# S07_PCIe_Connector.net
KiCad netlist of a schematic drawn in Altium Designer
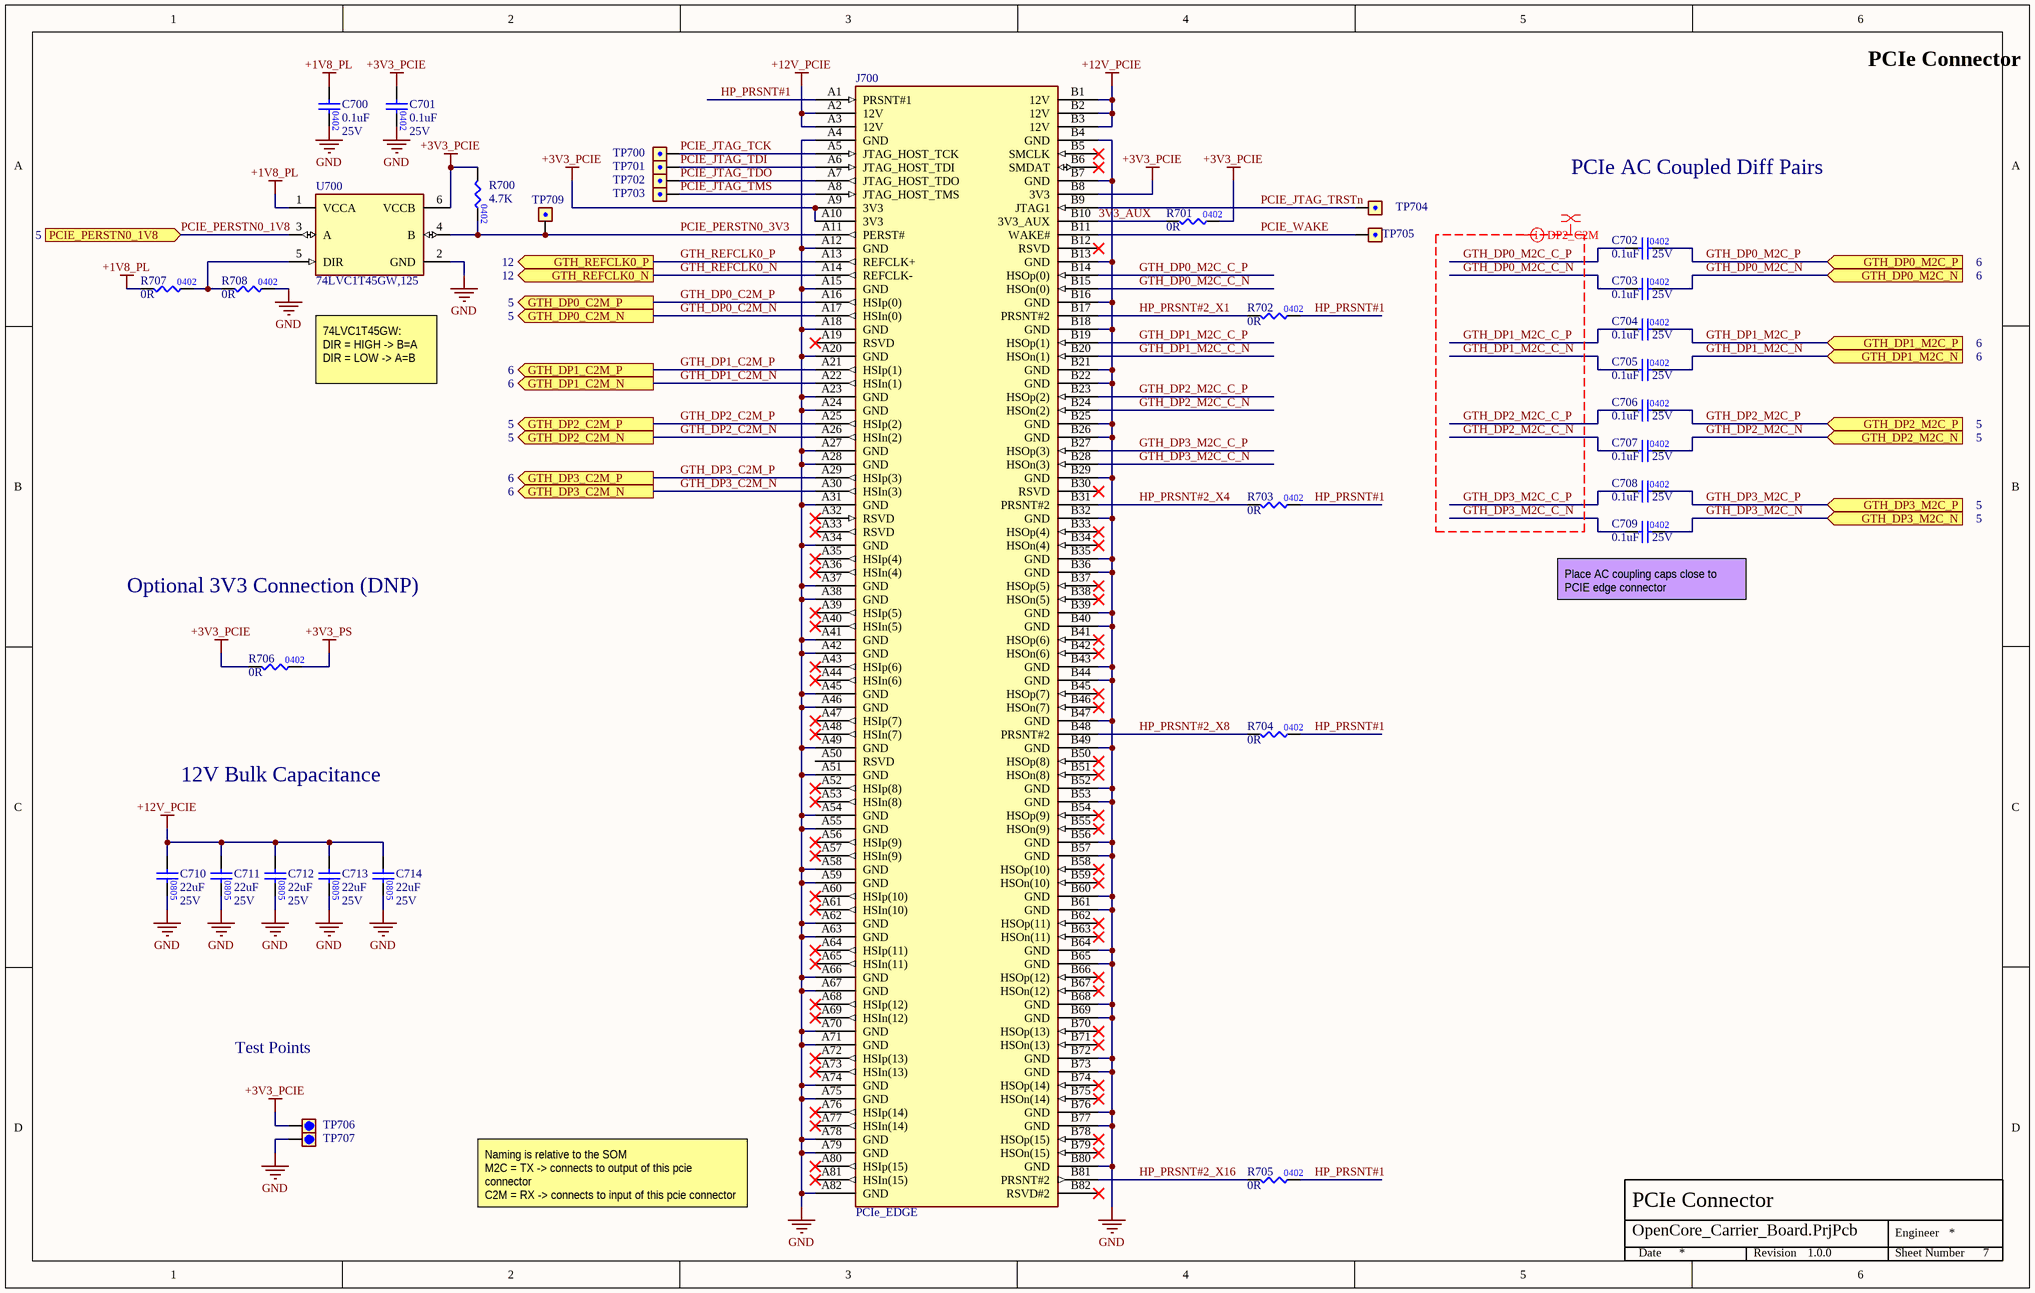
[diagram p0: S07_PCIe_Connector.SchDoc]

(export (version "E")
  (design (tool "Eeschema 10.0.6"))
  (components
    (comp (ref "C700")
      (value "0.1uF")
      (footprint "CAP0402")
      (description "CAP CER 0.1UF 25V X5R 0402")
      (fields
        (field (name "MANUFACTURER") "Samsung Electro-Mechanics")
        (field (name "TOLERANCE") "10%")
        (field (name "VOLTAGE RATING") "25V")
      )
      (libsource (lib "OpenCore_Sch_Lib") (part "CAP_CL05A104KA5NNNC"))
    )
    (comp (ref "C701")
      (value "0.1uF")
      (footprint "CAP0402")
      (description "CAP CER 0.1UF 25V X5R 0402")
      (fields
        (field (name "MANUFACTURER") "Samsung Electro-Mechanics")
        (field (name "TOLERANCE") "10%")
        (field (name "VOLTAGE RATING") "25V")
      )
      (libsource (lib "OpenCore_Sch_Lib") (part "CAP_CL05A104KA5NNNC"))
    )
    (comp (ref "C702")
      (value "0.1uF")
      (footprint "CAP0402")
      (description "CAP CER 0.1UF 25V X5R 0402")
      (fields
        (field (name "MANUFACTURER") "Samsung Electro-Mechanics")
        (field (name "TOLERANCE") "10%")
        (field (name "VOLTAGE RATING") "25V")
      )
      (libsource (lib "OpenCore_Sch_Lib") (part "CAP_CL05A104KA5NNNC"))
    )
    (comp (ref "C703")
      (value "0.1uF")
      (footprint "CAP0402")
      (description "CAP CER 0.1UF 25V X5R 0402")
      (fields
        (field (name "MANUFACTURER") "Samsung Electro-Mechanics")
        (field (name "TOLERANCE") "10%")
        (field (name "VOLTAGE RATING") "25V")
      )
      (libsource (lib "OpenCore_Sch_Lib") (part "CAP_CL05A104KA5NNNC"))
    )
    (comp (ref "C704")
      (value "0.1uF")
      (footprint "CAP0402")
      (description "CAP CER 0.1UF 25V X5R 0402")
      (fields
        (field (name "MANUFACTURER") "Samsung Electro-Mechanics")
        (field (name "TOLERANCE") "10%")
        (field (name "VOLTAGE RATING") "25V")
      )
      (libsource (lib "OpenCore_Sch_Lib") (part "CAP_CL05A104KA5NNNC"))
    )
    (comp (ref "C705")
      (value "0.1uF")
      (footprint "CAP0402")
      (description "CAP CER 0.1UF 25V X5R 0402")
      (fields
        (field (name "MANUFACTURER") "Samsung Electro-Mechanics")
        (field (name "TOLERANCE") "10%")
        (field (name "VOLTAGE RATING") "25V")
      )
      (libsource (lib "OpenCore_Sch_Lib") (part "CAP_CL05A104KA5NNNC"))
    )
    (comp (ref "C706")
      (value "0.1uF")
      (footprint "CAP0402")
      (description "CAP CER 0.1UF 25V X5R 0402")
      (fields
        (field (name "MANUFACTURER") "Samsung Electro-Mechanics")
        (field (name "TOLERANCE") "10%")
        (field (name "VOLTAGE RATING") "25V")
      )
      (libsource (lib "OpenCore_Sch_Lib") (part "CAP_CL05A104KA5NNNC"))
    )
    (comp (ref "C707")
      (value "0.1uF")
      (footprint "CAP0402")
      (description "CAP CER 0.1UF 25V X5R 0402")
      (fields
        (field (name "MANUFACTURER") "Samsung Electro-Mechanics")
        (field (name "TOLERANCE") "10%")
        (field (name "VOLTAGE RATING") "25V")
      )
      (libsource (lib "OpenCore_Sch_Lib") (part "CAP_CL05A104KA5NNNC"))
    )
    (comp (ref "C708")
      (value "0.1uF")
      (footprint "CAP0402")
      (description "CAP CER 0.1UF 25V X5R 0402")
      (fields
        (field (name "MANUFACTURER") "Samsung Electro-Mechanics")
        (field (name "TOLERANCE") "10%")
        (field (name "VOLTAGE RATING") "25V")
      )
      (libsource (lib "OpenCore_Sch_Lib") (part "CAP_CL05A104KA5NNNC"))
    )
    (comp (ref "C709")
      (value "0.1uF")
      (footprint "CAP0402")
      (description "CAP CER 0.1UF 25V X5R 0402")
      (fields
        (field (name "MANUFACTURER") "Samsung Electro-Mechanics")
        (field (name "TOLERANCE") "10%")
        (field (name "VOLTAGE RATING") "25V")
      )
      (libsource (lib "OpenCore_Sch_Lib") (part "CAP_CL05A104KA5NNNC"))
    )
    (comp (ref "C710")
      (value "22uF")
      (footprint "CAP0805")
      (description "CAP CER 22UF 25V X5R 0805")
      (fields
        (field (name "MANUFACTURER") "Samsung Electro-Mechanics")
        (field (name "TOLERANCE") "20%")
        (field (name "VOLTAGE RATING") "25V")
      )
      (libsource (lib "OpenCore_Sch_Lib") (part "CAP_CL21A226MAYNNNE"))
    )
    (comp (ref "C711")
      (value "22uF")
      (footprint "CAP0805")
      (description "CAP CER 22UF 25V X5R 0805")
      (fields
        (field (name "MANUFACTURER") "Samsung Electro-Mechanics")
        (field (name "TOLERANCE") "20%")
        (field (name "VOLTAGE RATING") "25V")
      )
      (libsource (lib "OpenCore_Sch_Lib") (part "CAP_CL21A226MAYNNNE"))
    )
    (comp (ref "C712")
      (value "22uF")
      (footprint "CAP0805")
      (description "CAP CER 22UF 25V X5R 0805")
      (fields
        (field (name "MANUFACTURER") "Samsung Electro-Mechanics")
        (field (name "TOLERANCE") "20%")
        (field (name "VOLTAGE RATING") "25V")
      )
      (libsource (lib "OpenCore_Sch_Lib") (part "CAP_CL21A226MAYNNNE"))
    )
    (comp (ref "C713")
      (value "22uF")
      (footprint "CAP0805")
      (description "CAP CER 22UF 25V X5R 0805")
      (fields
        (field (name "MANUFACTURER") "Samsung Electro-Mechanics")
        (field (name "TOLERANCE") "20%")
        (field (name "VOLTAGE RATING") "25V")
      )
      (libsource (lib "OpenCore_Sch_Lib") (part "CAP_CL21A226MAYNNNE"))
    )
    (comp (ref "C714")
      (value "22uF")
      (footprint "CAP0805")
      (description "CAP CER 22UF 25V X5R 0805")
      (fields
        (field (name "MANUFACTURER") "Samsung Electro-Mechanics")
        (field (name "TOLERANCE") "20%")
        (field (name "VOLTAGE RATING") "25V")
      )
      (libsource (lib "OpenCore_Sch_Lib") (part "CAP_CL21A226MAYNNNE"))
    )
    (comp (ref "J700")
      (value "PCIe_EDGE")
      (footprint "PCIe")
      (description "PCIe 3.3V x16")
      (libsource (lib "OpenCore_Sch_Lib") (part "PCIe_EDGE"))
    )
    (comp (ref "R700")
      (value "RES_0402")
      (footprint "RES0402")
      (description "RES 4.7K OHM 1% 1/16W 0402")
      (fields
        (field (name "MANUFACTURER") "YAGEO")
        (field (name "MANUFACTURER PART NUMBER") "RC0402FR-074K7L")
        (field (name "RESISTANCE") "4.7K")
      )
      (libsource (lib "OpenCore_Sch_Lib") (part ".RES_RC0402FR-074K7L"))
    )
    (comp (ref "R701")
      (value "RES_0402")
      (footprint "RES0402")
      (description "RES 0 OHM JUMPER 1/16W 0402")
      (fields
        (field (name "MANUFACTURER") "YAGEO")
        (field (name "MANUFACTURER PART NUMBER") "RC0402JR-070RL")
        (field (name "RESISTANCE") "0R")
      )
      (libsource (lib "OpenCore_Sch_Lib") (part ".RES_RC0402JR-070RL"))
    )
    (comp (ref "R702")
      (value "RES_0402")
      (footprint "RES0402")
      (description "RES 0 OHM JUMPER 1/16W 0402")
      (fields
        (field (name "MANUFACTURER") "YAGEO")
        (field (name "MANUFACTURER PART NUMBER") "RC0402JR-070RL")
        (field (name "RESISTANCE") "0R")
      )
      (libsource (lib "OpenCore_Sch_Lib") (part ".RES_RC0402JR-070RL"))
    )
    (comp (ref "R703")
      (value "RES_0402")
      (footprint "RES0402")
      (description "RES 0 OHM JUMPER 1/16W 0402")
      (fields
        (field (name "MANUFACTURER") "YAGEO")
        (field (name "MANUFACTURER PART NUMBER") "RC0402JR-070RL")
        (field (name "RESISTANCE") "0R")
      )
      (libsource (lib "OpenCore_Sch_Lib") (part ".RES_RC0402JR-070RL"))
    )
    (comp (ref "R704")
      (value "RES_0402")
      (footprint "RES0402")
      (description "RES 0 OHM JUMPER 1/16W 0402")
      (fields
        (field (name "MANUFACTURER") "YAGEO")
        (field (name "MANUFACTURER PART NUMBER") "RC0402JR-070RL")
        (field (name "RESISTANCE") "0R")
      )
      (libsource (lib "OpenCore_Sch_Lib") (part ".RES_RC0402JR-070RL"))
    )
    (comp (ref "R705")
      (value "RES_0402")
      (footprint "RES0402")
      (description "RES 0 OHM JUMPER 1/16W 0402")
      (fields
        (field (name "MANUFACTURER") "YAGEO")
        (field (name "MANUFACTURER PART NUMBER") "RC0402JR-070RL")
        (field (name "RESISTANCE") "0R")
      )
      (libsource (lib "OpenCore_Sch_Lib") (part ".RES_RC0402JR-070RL"))
    )
    (comp (ref "R706")
      (value "RES_0402")
      (footprint "RES0402")
      (description "RES 0 OHM JUMPER 1/16W 0402")
      (fields
        (field (name "MANUFACTURER") "YAGEO")
        (field (name "MANUFACTURER PART NUMBER") "RC0402JR-070RL")
        (field (name "RESISTANCE") "0R")
      )
      (libsource (lib "OpenCore_Sch_Lib") (part ".RES_RC0402JR-070RL"))
    )
    (comp (ref "R707")
      (value "RES_0402")
      (footprint "RES0402")
      (description "RES 0 OHM JUMPER 1/16W 0402")
      (fields
        (field (name "MANUFACTURER") "YAGEO")
        (field (name "MANUFACTURER PART NUMBER") "RC0402JR-070RL")
        (field (name "RESISTANCE") "0R")
      )
      (libsource (lib "OpenCore_Sch_Lib") (part ".RES_RC0402JR-070RL"))
    )
    (comp (ref "R708")
      (value "RES_0402")
      (footprint "RES0402")
      (description "RES 0 OHM JUMPER 1/16W 0402")
      (fields
        (field (name "MANUFACTURER") "YAGEO")
        (field (name "MANUFACTURER PART NUMBER") "RC0402JR-070RL")
        (field (name "RESISTANCE") "0R")
      )
      (libsource (lib "OpenCore_Sch_Lib") (part ".RES_RC0402JR-070RL"))
    )
    (comp (ref "TP700")
      (value "1mm Round Pad Testpoint")
      (footprint "TP_1MM")
      (libsource (lib "") (part "TP_1MM_1"))
    )
    (comp (ref "TP701")
      (value "1mm Round Pad Testpoint")
      (footprint "TP_1MM")
      (libsource (lib "") (part "TP_1MM_1"))
    )
    (comp (ref "TP702")
      (value "1mm Round Pad Testpoint")
      (footprint "TP_1MM")
      (libsource (lib "") (part "TP_1MM_1"))
    )
    (comp (ref "TP703")
      (value "1mm Round Pad Testpoint")
      (footprint "TP_1MM")
      (libsource (lib "") (part "TP_1MM_1"))
    )
    (comp (ref "TP704")
      (value "1mm Round Pad Testpoint")
      (footprint "TP_1MM")
      (libsource (lib "OpenCore_Sch_Lib") (part "TP_1MM"))
    )
    (comp (ref "TP705")
      (value "1mm Round Pad Testpoint")
      (footprint "TP_1MM")
      (libsource (lib "OpenCore_Sch_Lib") (part "TP_1MM"))
    )
    (comp (ref "TP706")
      (value "2mm Round Pad Testpoint")
      (footprint "TP_2MM")
      (libsource (lib "OpenCore_Sch_Lib") (part "TP_2MM"))
    )
    (comp (ref "TP707")
      (value "2mm Round Pad Testpoint")
      (footprint "TP_2MM")
      (libsource (lib "OpenCore_Sch_Lib") (part "TP_2MM"))
    )
    (comp (ref "TP709")
      (value "1mm Round Pad Testpoint")
      (footprint "TP_1MM")
      (libsource (lib "OpenCore_Sch_Lib") (part "TP_1MM"))
    )
    (comp (ref "U700")
      (value "74LVC1T45GW,125")
      (footprint "NEXPERIA_TSSOP6")
      (description "IC TRANSLTR BIDIRECTIONAL 6TSSOP")
      (libsource (lib "OpenCore_Sch_Lib") (part "74LVC1T45GW,125"))
    )
  )
  (nets
    (net (code "1") (name "+1V8_PL") (class "Default")
      (node (ref "C700") (pin "1") (pinfunction "1_1") (pintype "passive"))
      (node (ref "R707") (pin "1") (pinfunction "1_1") (pintype "passive"))
      (node (ref "U700") (pin "1") (pinfunction "VCCA_1") (pintype "power_in"))
    )
    (net (code "2") (name "+3V3_PCIE") (class "Default")
      (node (ref "C701") (pin "1") (pinfunction "1_1") (pintype "passive"))
      (node (ref "J700") (pin "A10") (pinfunction "3V3_A10") (pintype "power_in"))
      (node (ref "J700") (pin "A9") (pinfunction "3V3_A9") (pintype "power_in"))
      (node (ref "J700") (pin "B8") (pinfunction "3V3_B8") (pintype "power_in"))
      (node (ref "R700") (pin "1") (pinfunction "1_1") (pintype "passive"))
      (node (ref "R701") (pin "2") (pinfunction "2_2") (pintype "passive"))
      (node (ref "R706") (pin "1") (pinfunction "1_1") (pintype "passive"))
      (node (ref "TP706") (pin "1") (pinfunction "1_1") (pintype "passive"))
      (node (ref "U700") (pin "6") (pinfunction "VCCB_6") (pintype "power_in"))
    )
    (net (code "3") (name "+3V3_PS") (class "Default")
      (node (ref "R706") (pin "2") (pinfunction "2_2") (pintype "passive"))
    )
    (net (code "4") (name "+12V_PCIE") (class "Default")
      (node (ref "C710") (pin "1") (pinfunction "1_1") (pintype "passive"))
      (node (ref "C711") (pin "1") (pinfunction "1_1") (pintype "passive"))
      (node (ref "C712") (pin "1") (pinfunction "1_1") (pintype "passive"))
      (node (ref "C713") (pin "1") (pinfunction "1_1") (pintype "passive"))
      (node (ref "C714") (pin "1") (pinfunction "1_1") (pintype "passive"))
      (node (ref "J700") (pin "A2") (pinfunction "12V_A2") (pintype "power_in"))
      (node (ref "J700") (pin "A3") (pinfunction "12V_A3") (pintype "power_in"))
      (node (ref "J700") (pin "B1") (pinfunction "12V_B1") (pintype "power_in"))
      (node (ref "J700") (pin "B2") (pinfunction "12V_B2") (pintype "power_in"))
      (node (ref "J700") (pin "B3") (pinfunction "12V_B3") (pintype "power_in"))
    )
    (net (code "5") (name "/3V3_AUX") (class "Default")
      (node (ref "J700") (pin "B10") (pinfunction "3V3_AUX_B10") (pintype "power_in"))
      (node (ref "R701") (pin "1") (pinfunction "1_1") (pintype "passive"))
    )
    (net (code "6") (name "/GTH_DP0_C2M_N") (class "Default")
      (node (ref "J700") (pin "A17") (pinfunction "HSIn(0)_A17") (pintype "output"))
    )
    (net (code "7") (name "/GTH_DP0_C2M_P") (class "Default")
      (node (ref "J700") (pin "A16") (pinfunction "HSIp(0)_A16") (pintype "output"))
    )
    (net (code "8") (name "/GTH_DP0_M2C_C_N") (class "Default")
      (node (ref "C703") (pin "1") (pinfunction "1_1") (pintype "passive"))
      (node (ref "J700") (pin "B15") (pinfunction "HSOn(0)_B15") (pintype "input"))
    )
    (net (code "9") (name "/GTH_DP0_M2C_C_P") (class "Default")
      (node (ref "C702") (pin "1") (pinfunction "1_1") (pintype "passive"))
      (node (ref "J700") (pin "B14") (pinfunction "HSOp(0)_B14") (pintype "input"))
    )
    (net (code "10") (name "/GTH_DP0_M2C_N") (class "Default")
      (node (ref "C703") (pin "2") (pinfunction "2_2") (pintype "passive"))
    )
    (net (code "11") (name "/GTH_DP0_M2C_P") (class "Default")
      (node (ref "C702") (pin "2") (pinfunction "2_2") (pintype "passive"))
    )
    (net (code "12") (name "/GTH_DP1_C2M_N") (class "Default")
      (node (ref "J700") (pin "A22") (pinfunction "HSIn(1)_A22") (pintype "output"))
    )
    (net (code "13") (name "/GTH_DP1_C2M_P") (class "Default")
      (node (ref "J700") (pin "A21") (pinfunction "HSIp(1)_A21") (pintype "output"))
    )
    (net (code "14") (name "/GTH_DP1_M2C_C_N") (class "Default")
      (node (ref "C705") (pin "1") (pinfunction "1_1") (pintype "passive"))
      (node (ref "J700") (pin "B20") (pinfunction "HSOn(1)_B20") (pintype "input"))
    )
    (net (code "15") (name "/GTH_DP1_M2C_C_P") (class "Default")
      (node (ref "C704") (pin "1") (pinfunction "1_1") (pintype "passive"))
      (node (ref "J700") (pin "B19") (pinfunction "HSOp(1)_B19") (pintype "input"))
    )
    (net (code "16") (name "/GTH_DP1_M2C_N") (class "Default")
      (node (ref "C705") (pin "2") (pinfunction "2_2") (pintype "passive"))
    )
    (net (code "17") (name "/GTH_DP1_M2C_P") (class "Default")
      (node (ref "C704") (pin "2") (pinfunction "2_2") (pintype "passive"))
    )
    (net (code "18") (name "/GTH_DP2_C2M_N") (class "Default")
      (node (ref "J700") (pin "A26") (pinfunction "HSIn(2)_A26") (pintype "output"))
    )
    (net (code "19") (name "/GTH_DP2_C2M_P") (class "Default")
      (node (ref "J700") (pin "A25") (pinfunction "HSIp(2)_A25") (pintype "output"))
    )
    (net (code "20") (name "/GTH_DP2_M2C_C_N") (class "Default")
      (node (ref "C707") (pin "1") (pinfunction "1_1") (pintype "passive"))
      (node (ref "J700") (pin "B24") (pinfunction "HSOn(2)_B24") (pintype "input"))
    )
    (net (code "21") (name "/GTH_DP2_M2C_C_P") (class "Default")
      (node (ref "C706") (pin "1") (pinfunction "1_1") (pintype "passive"))
      (node (ref "J700") (pin "B23") (pinfunction "HSOp(2)_B23") (pintype "input"))
    )
    (net (code "22") (name "/GTH_DP2_M2C_N") (class "Default")
      (node (ref "C707") (pin "2") (pinfunction "2_2") (pintype "passive"))
    )
    (net (code "23") (name "/GTH_DP2_M2C_P") (class "Default")
      (node (ref "C706") (pin "2") (pinfunction "2_2") (pintype "passive"))
    )
    (net (code "24") (name "/GTH_DP3_C2M_N") (class "Default")
      (node (ref "J700") (pin "A30") (pinfunction "HSIn(3)_A30") (pintype "output"))
    )
    (net (code "25") (name "/GTH_DP3_C2M_P") (class "Default")
      (node (ref "J700") (pin "A29") (pinfunction "HSIp(3)_A29") (pintype "output"))
    )
    (net (code "26") (name "/GTH_DP3_M2C_C_N") (class "Default")
      (node (ref "C709") (pin "1") (pinfunction "1_1") (pintype "passive"))
      (node (ref "J700") (pin "B28") (pinfunction "HSOn(3)_B28") (pintype "input"))
    )
    (net (code "27") (name "/GTH_DP3_M2C_C_P") (class "Default")
      (node (ref "C708") (pin "1") (pinfunction "1_1") (pintype "passive"))
      (node (ref "J700") (pin "B27") (pinfunction "HSOp(3)_B27") (pintype "input"))
    )
    (net (code "28") (name "/GTH_DP3_M2C_N") (class "Default")
      (node (ref "C709") (pin "2") (pinfunction "2_2") (pintype "passive"))
    )
    (net (code "29") (name "/GTH_DP3_M2C_P") (class "Default")
      (node (ref "C708") (pin "2") (pinfunction "2_2") (pintype "passive"))
    )
    (net (code "30") (name "/GTH_REFCLK0_N") (class "Default")
      (node (ref "J700") (pin "A14") (pinfunction "REFCLK-_A14") (pintype "output"))
    )
    (net (code "31") (name "/GTH_REFCLK0_P") (class "Default")
      (node (ref "J700") (pin "A13") (pinfunction "REFCLK+_A13") (pintype "output"))
    )
    (net (code "32") (name "/HP_PRSNT#1") (class "Default")
      (node (ref "J700") (pin "A1") (pinfunction "PRSNT#1_A1") (pintype "input"))
      (node (ref "R702") (pin "2") (pinfunction "2_2") (pintype "passive"))
      (node (ref "R703") (pin "2") (pinfunction "2_2") (pintype "passive"))
      (node (ref "R704") (pin "2") (pinfunction "2_2") (pintype "passive"))
      (node (ref "R705") (pin "2") (pinfunction "2_2") (pintype "passive"))
    )
    (net (code "33") (name "/HP_PRSNT#2_X1") (class "Default")
      (node (ref "J700") (pin "B17") (pinfunction "PRSNT#2_B17") (pintype "passive"))
      (node (ref "R702") (pin "1") (pinfunction "1_1") (pintype "passive"))
    )
    (net (code "34") (name "/HP_PRSNT#2_X4") (class "Default")
      (node (ref "J700") (pin "B31") (pinfunction "PRSNT#2_B31") (pintype "passive"))
      (node (ref "R703") (pin "1") (pinfunction "1_1") (pintype "passive"))
    )
    (net (code "35") (name "/HP_PRSNT#2_X8") (class "Default")
      (node (ref "J700") (pin "B48") (pinfunction "PRSNT#2_B48") (pintype "passive"))
      (node (ref "R704") (pin "1") (pinfunction "1_1") (pintype "passive"))
    )
    (net (code "36") (name "/HP_PRSNT#2_X16") (class "Default")
      (node (ref "J700") (pin "B81") (pinfunction "PRSNT#2_B81") (pintype "output"))
      (node (ref "R705") (pin "1") (pinfunction "1_1") (pintype "passive"))
    )
    (net (code "37") (name "/PCIE_JTAG_TCK") (class "Default")
      (node (ref "J700") (pin "A5") (pinfunction "JTAG_HOST_TCK_A5") (pintype "input"))
      (node (ref "TP700") (pin "1") (pinfunction "1_1") (pintype "passive"))
    )
    (net (code "38") (name "/PCIE_JTAG_TDI") (class "Default")
      (node (ref "J700") (pin "A6") (pinfunction "JTAG_HOST_TDI_A6") (pintype "input"))
      (node (ref "TP701") (pin "1") (pinfunction "1_1") (pintype "passive"))
    )
    (net (code "39") (name "/PCIE_JTAG_TDO") (class "Default")
      (node (ref "J700") (pin "A7") (pinfunction "JTAG_HOST_TDO_A7") (pintype "output"))
      (node (ref "TP702") (pin "1") (pinfunction "1_1") (pintype "passive"))
    )
    (net (code "40") (name "/PCIE_JTAG_TMS") (class "Default")
      (node (ref "J700") (pin "A8") (pinfunction "JTAG_HOST_TMS_A8") (pintype "input"))
      (node (ref "TP703") (pin "1") (pinfunction "1_1") (pintype "passive"))
    )
    (net (code "41") (name "/PCIE_JTAG_TRSTn") (class "Default")
      (node (ref "J700") (pin "B9") (pinfunction "JTAG1_B9") (pintype "input"))
      (node (ref "TP704") (pin "1") (pinfunction "1_1") (pintype "passive"))
    )
    (net (code "42") (name "/PCIE_PERSTN0_1V8") (class "Default")
      (node (ref "U700") (pin "3") (pinfunction "A_3") (pintype "bidirectional"))
    )
    (net (code "43") (name "/PCIE_PERSTN0_3V3") (class "Default")
      (node (ref "J700") (pin "A11") (pinfunction "PERST#_A11") (pintype "output"))
      (node (ref "R700") (pin "2") (pinfunction "2_2") (pintype "passive"))
      (node (ref "TP709") (pin "1") (pinfunction "1_1") (pintype "passive"))
      (node (ref "U700") (pin "4") (pinfunction "B_4") (pintype "bidirectional"))
    )
    (net (code "44") (name "/PCIE_WAKE") (class "Default")
      (node (ref "J700") (pin "B11") (pinfunction "WAKE#_B11") (pintype "passive"))
      (node (ref "TP705") (pin "1") (pinfunction "1_1") (pintype "passive"))
    )
    (net (code "45") (name "GND") (class "Default")
      (node (ref "C700") (pin "2") (pinfunction "2_2") (pintype "passive"))
      (node (ref "C701") (pin "2") (pinfunction "2_2") (pintype "passive"))
      (node (ref "C710") (pin "2") (pinfunction "2_2") (pintype "passive"))
      (node (ref "C711") (pin "2") (pinfunction "2_2") (pintype "passive"))
      (node (ref "C712") (pin "2") (pinfunction "2_2") (pintype "passive"))
      (node (ref "C713") (pin "2") (pinfunction "2_2") (pintype "passive"))
      (node (ref "C714") (pin "2") (pinfunction "2_2") (pintype "passive"))
      (node (ref "J700") (pin "A12") (pinfunction "GND_A12") (pintype "power_in"))
      (node (ref "J700") (pin "A15") (pinfunction "GND_A15") (pintype "power_in"))
      (node (ref "J700") (pin "A18") (pinfunction "GND_A18") (pintype "power_in"))
      (node (ref "J700") (pin "A20") (pinfunction "GND_A20") (pintype "power_in"))
      (node (ref "J700") (pin "A23") (pinfunction "GND_A23") (pintype "power_in"))
      (node (ref "J700") (pin "A24") (pinfunction "GND_A24") (pintype "power_in"))
      (node (ref "J700") (pin "A27") (pinfunction "GND_A27") (pintype "power_in"))
      (node (ref "J700") (pin "A28") (pinfunction "GND_A28") (pintype "power_in"))
      (node (ref "J700") (pin "A31") (pinfunction "GND_A31") (pintype "power_in"))
      (node (ref "J700") (pin "A34") (pinfunction "GND_A34") (pintype "power_in"))
      (node (ref "J700") (pin "A37") (pinfunction "GND_A37") (pintype "power_in"))
      (node (ref "J700") (pin "A38") (pinfunction "GND_A38") (pintype "power_in"))
      (node (ref "J700") (pin "A4") (pinfunction "GND_A4") (pintype "power_in"))
      (node (ref "J700") (pin "A41") (pinfunction "GND_A41") (pintype "power_in"))
      (node (ref "J700") (pin "A42") (pinfunction "GND_A42") (pintype "power_in"))
      (node (ref "J700") (pin "A45") (pinfunction "GND_A45") (pintype "power_in"))
      (node (ref "J700") (pin "A46") (pinfunction "GND_A46") (pintype "power_in"))
      (node (ref "J700") (pin "A49") (pinfunction "GND_A49") (pintype "power_in"))
      (node (ref "J700") (pin "A51") (pinfunction "GND_A51") (pintype "power_in"))
      (node (ref "J700") (pin "A54") (pinfunction "GND_A54") (pintype "power_in"))
      (node (ref "J700") (pin "A55") (pinfunction "GND_A55") (pintype "power_in"))
      (node (ref "J700") (pin "A58") (pinfunction "GND_A58") (pintype "power_in"))
      (node (ref "J700") (pin "A59") (pinfunction "GND_A59") (pintype "power_in"))
      (node (ref "J700") (pin "A62") (pinfunction "GND_A62") (pintype "power_in"))
      (node (ref "J700") (pin "A63") (pinfunction "GND_A63") (pintype "power_in"))
      (node (ref "J700") (pin "A66") (pinfunction "GND_A66") (pintype "power_in"))
      (node (ref "J700") (pin "A67") (pinfunction "GND_A67") (pintype "power_in"))
      (node (ref "J700") (pin "A70") (pinfunction "GND_A70") (pintype "power_in"))
      (node (ref "J700") (pin "A71") (pinfunction "GND_A71") (pintype "power_in"))
      (node (ref "J700") (pin "A74") (pinfunction "GND_A74") (pintype "power_in"))
      (node (ref "J700") (pin "A75") (pinfunction "GND_A75") (pintype "power_in"))
      (node (ref "J700") (pin "A78") (pinfunction "GND_A78") (pintype "power_in"))
      (node (ref "J700") (pin "A79") (pinfunction "GND_A79") (pintype "power_in"))
      (node (ref "J700") (pin "A82") (pinfunction "GND_A82") (pintype "power_in"))
      (node (ref "J700") (pin "B13") (pinfunction "GND_B13") (pintype "power_in"))
      (node (ref "J700") (pin "B16") (pinfunction "GND_B16") (pintype "power_in"))
      (node (ref "J700") (pin "B18") (pinfunction "GND_B18") (pintype "power_in"))
      (node (ref "J700") (pin "B21") (pinfunction "GND_B21") (pintype "power_in"))
      (node (ref "J700") (pin "B22") (pinfunction "GND_B22") (pintype "power_in"))
      (node (ref "J700") (pin "B25") (pinfunction "GND_B25") (pintype "power_in"))
      (node (ref "J700") (pin "B26") (pinfunction "GND_B26") (pintype "power_in"))
      (node (ref "J700") (pin "B29") (pinfunction "GND_B29") (pintype "power_in"))
      (node (ref "J700") (pin "B32") (pinfunction "GND_B32") (pintype "power_in"))
      (node (ref "J700") (pin "B35") (pinfunction "GND_B35") (pintype "power_in"))
      (node (ref "J700") (pin "B36") (pinfunction "GND_B36") (pintype "power_in"))
      (node (ref "J700") (pin "B39") (pinfunction "GND_B39") (pintype "power_in"))
      (node (ref "J700") (pin "B4") (pinfunction "GND_B4") (pintype "power_in"))
      (node (ref "J700") (pin "B40") (pinfunction "GND_B40") (pintype "power_in"))
      (node (ref "J700") (pin "B43") (pinfunction "GND_B43") (pintype "power_in"))
      (node (ref "J700") (pin "B44") (pinfunction "GND_B44") (pintype "power_in"))
      (node (ref "J700") (pin "B47") (pinfunction "GND_B47") (pintype "power_in"))
      (node (ref "J700") (pin "B49") (pinfunction "GND_B49") (pintype "power_in"))
      (node (ref "J700") (pin "B52") (pinfunction "GND_B52") (pintype "power_in"))
      (node (ref "J700") (pin "B53") (pinfunction "GND_B53") (pintype "power_in"))
      (node (ref "J700") (pin "B56") (pinfunction "GND_B56") (pintype "power_in"))
      (node (ref "J700") (pin "B57") (pinfunction "GND_B57") (pintype "power_in"))
      (node (ref "J700") (pin "B60") (pinfunction "GND_B60") (pintype "power_in"))
      (node (ref "J700") (pin "B61") (pinfunction "GND_B61") (pintype "power_in"))
      (node (ref "J700") (pin "B64") (pinfunction "GND_B64") (pintype "power_in"))
      (node (ref "J700") (pin "B65") (pinfunction "GND_B65") (pintype "power_in"))
      (node (ref "J700") (pin "B68") (pinfunction "GND_B68") (pintype "power_in"))
      (node (ref "J700") (pin "B69") (pinfunction "GND_B69") (pintype "power_in"))
      (node (ref "J700") (pin "B7") (pinfunction "GND_B7") (pintype "power_in"))
      (node (ref "J700") (pin "B72") (pinfunction "GND_B72") (pintype "power_in"))
      (node (ref "J700") (pin "B73") (pinfunction "GND_B73") (pintype "power_in"))
      (node (ref "J700") (pin "B76") (pinfunction "GND_B76") (pintype "power_in"))
      (node (ref "J700") (pin "B77") (pinfunction "GND_B77") (pintype "power_in"))
      (node (ref "J700") (pin "B80") (pinfunction "GND_B80") (pintype "power_in"))
      (node (ref "R708") (pin "2") (pinfunction "2_2") (pintype "passive"))
      (node (ref "TP707") (pin "1") (pinfunction "1_1") (pintype "passive"))
      (node (ref "U700") (pin "2") (pinfunction "GND_2") (pintype "power_in"))
    )
    (net (code "46") (name "Net-(U700-DIR)") (class "Default")
      (node (ref "R707") (pin "2") (pinfunction "2_2") (pintype "passive"))
      (node (ref "R708") (pin "1") (pinfunction "1_1") (pintype "passive"))
      (node (ref "U700") (pin "5") (pinfunction "DIR_5") (pintype "input"))
    )
    (net (code "47") (name "unconnected-(J700-HSIn(4)-PadA36)") (class "Default")
      (node (ref "J700") (pin "A36") (pinfunction "HSIn(4)_A36") (pintype "output+no_connect"))
    )
    (net (code "48") (name "unconnected-(J700-HSIn(5)-PadA40)") (class "Default")
      (node (ref "J700") (pin "A40") (pinfunction "HSIn(5)_A40") (pintype "output+no_connect"))
    )
    (net (code "49") (name "unconnected-(J700-HSIn(6)-PadA44)") (class "Default")
      (node (ref "J700") (pin "A44") (pinfunction "HSIn(6)_A44") (pintype "output+no_connect"))
    )
    (net (code "50") (name "unconnected-(J700-HSIn(7)-PadA48)") (class "Default")
      (node (ref "J700") (pin "A48") (pinfunction "HSIn(7)_A48") (pintype "output+no_connect"))
    )
    (net (code "51") (name "unconnected-(J700-HSIn(8)-PadA53)") (class "Default")
      (node (ref "J700") (pin "A53") (pinfunction "HSIn(8)_A53") (pintype "output+no_connect"))
    )
    (net (code "52") (name "unconnected-(J700-HSIn(9)-PadA57)") (class "Default")
      (node (ref "J700") (pin "A57") (pinfunction "HSIn(9)_A57") (pintype "output+no_connect"))
    )
    (net (code "53") (name "unconnected-(J700-HSIn(10)-PadA61)") (class "Default")
      (node (ref "J700") (pin "A61") (pinfunction "HSIn(10)_A61") (pintype "output+no_connect"))
    )
    (net (code "54") (name "unconnected-(J700-HSIn(11)-PadA65)") (class "Default")
      (node (ref "J700") (pin "A65") (pinfunction "HSIn(11)_A65") (pintype "output+no_connect"))
    )
    (net (code "55") (name "unconnected-(J700-HSIn(12)-PadA69)") (class "Default")
      (node (ref "J700") (pin "A69") (pinfunction "HSIn(12)_A69") (pintype "output+no_connect"))
    )
    (net (code "56") (name "unconnected-(J700-HSIn(13)-PadA73)") (class "Default")
      (node (ref "J700") (pin "A73") (pinfunction "HSIn(13)_A73") (pintype "output+no_connect"))
    )
    (net (code "57") (name "unconnected-(J700-HSIn(14)-PadA77)") (class "Default")
      (node (ref "J700") (pin "A77") (pinfunction "HSIn(14)_A77") (pintype "output+no_connect"))
    )
    (net (code "58") (name "unconnected-(J700-HSIn(15)-PadA81)") (class "Default")
      (node (ref "J700") (pin "A81") (pinfunction "HSIn(15)_A81") (pintype "output+no_connect"))
    )
    (net (code "59") (name "unconnected-(J700-HSIp(4)-PadA35)") (class "Default")
      (node (ref "J700") (pin "A35") (pinfunction "HSIp(4)_A35") (pintype "output+no_connect"))
    )
    (net (code "60") (name "unconnected-(J700-HSIp(5)-PadA39)") (class "Default")
      (node (ref "J700") (pin "A39") (pinfunction "HSIp(5)_A39") (pintype "output+no_connect"))
    )
    (net (code "61") (name "unconnected-(J700-HSIp(6)-PadA43)") (class "Default")
      (node (ref "J700") (pin "A43") (pinfunction "HSIp(6)_A43") (pintype "output+no_connect"))
    )
    (net (code "62") (name "unconnected-(J700-HSIp(7)-PadA47)") (class "Default")
      (node (ref "J700") (pin "A47") (pinfunction "HSIp(7)_A47") (pintype "output+no_connect"))
    )
    (net (code "63") (name "unconnected-(J700-HSIp(8)-PadA52)") (class "Default")
      (node (ref "J700") (pin "A52") (pinfunction "HSIp(8)_A52") (pintype "output+no_connect"))
    )
    (net (code "64") (name "unconnected-(J700-HSIp(9)-PadA56)") (class "Default")
      (node (ref "J700") (pin "A56") (pinfunction "HSIp(9)_A56") (pintype "output+no_connect"))
    )
    (net (code "65") (name "unconnected-(J700-HSIp(10)-PadA60)") (class "Default")
      (node (ref "J700") (pin "A60") (pinfunction "HSIp(10)_A60") (pintype "output+no_connect"))
    )
    (net (code "66") (name "unconnected-(J700-HSIp(11)-PadA64)") (class "Default")
      (node (ref "J700") (pin "A64") (pinfunction "HSIp(11)_A64") (pintype "output+no_connect"))
    )
    (net (code "67") (name "unconnected-(J700-HSIp(12)-PadA68)") (class "Default")
      (node (ref "J700") (pin "A68") (pinfunction "HSIp(12)_A68") (pintype "output+no_connect"))
    )
    (net (code "68") (name "unconnected-(J700-HSIp(13)-PadA72)") (class "Default")
      (node (ref "J700") (pin "A72") (pinfunction "HSIp(13)_A72") (pintype "output+no_connect"))
    )
    (net (code "69") (name "unconnected-(J700-HSIp(14)-PadA76)") (class "Default")
      (node (ref "J700") (pin "A76") (pinfunction "HSIp(14)_A76") (pintype "output+no_connect"))
    )
    (net (code "70") (name "unconnected-(J700-HSIp(15)-PadA80)") (class "Default")
      (node (ref "J700") (pin "A80") (pinfunction "HSIp(15)_A80") (pintype "output+no_connect"))
    )
    (net (code "71") (name "unconnected-(J700-HSOn(4)-PadB34)") (class "Default")
      (node (ref "J700") (pin "B34") (pinfunction "HSOn(4)_B34") (pintype "input+no_connect"))
    )
    (net (code "72") (name "unconnected-(J700-HSOn(5)-PadB38)") (class "Default")
      (node (ref "J700") (pin "B38") (pinfunction "HSOn(5)_B38") (pintype "input+no_connect"))
    )
    (net (code "73") (name "unconnected-(J700-HSOn(6)-PadB42)") (class "Default")
      (node (ref "J700") (pin "B42") (pinfunction "HSOn(6)_B42") (pintype "input+no_connect"))
    )
    (net (code "74") (name "unconnected-(J700-HSOn(7)-PadB46)") (class "Default")
      (node (ref "J700") (pin "B46") (pinfunction "HSOn(7)_B46") (pintype "input+no_connect"))
    )
    (net (code "75") (name "unconnected-(J700-HSOn(8)-PadB51)") (class "Default")
      (node (ref "J700") (pin "B51") (pinfunction "HSOn(8)_B51") (pintype "input+no_connect"))
    )
    (net (code "76") (name "unconnected-(J700-HSOn(9)-PadB55)") (class "Default")
      (node (ref "J700") (pin "B55") (pinfunction "HSOn(9)_B55") (pintype "input+no_connect"))
    )
    (net (code "77") (name "unconnected-(J700-HSOn(10)-PadB59)") (class "Default")
      (node (ref "J700") (pin "B59") (pinfunction "HSOn(10)_B59") (pintype "input+no_connect"))
    )
    (net (code "78") (name "unconnected-(J700-HSOn(11)-PadB63)") (class "Default")
      (node (ref "J700") (pin "B63") (pinfunction "HSOn(11)_B63") (pintype "input+no_connect"))
    )
    (net (code "79") (name "unconnected-(J700-HSOn(12)-PadB67)") (class "Default")
      (node (ref "J700") (pin "B67") (pinfunction "HSOn(12)_B67") (pintype "input+no_connect"))
    )
    (net (code "80") (name "unconnected-(J700-HSOn(13)-PadB71)") (class "Default")
      (node (ref "J700") (pin "B71") (pinfunction "HSOn(13)_B71") (pintype "input+no_connect"))
    )
    (net (code "81") (name "unconnected-(J700-HSOn(14)-PadB75)") (class "Default")
      (node (ref "J700") (pin "B75") (pinfunction "HSOn(14)_B75") (pintype "input+no_connect"))
    )
    (net (code "82") (name "unconnected-(J700-HSOn(15)-PadB79)") (class "Default")
      (node (ref "J700") (pin "B79") (pinfunction "HSOn(15)_B79") (pintype "input+no_connect"))
    )
    (net (code "83") (name "unconnected-(J700-HSOp(4)-PadB33)") (class "Default")
      (node (ref "J700") (pin "B33") (pinfunction "HSOp(4)_B33") (pintype "input+no_connect"))
    )
    (net (code "84") (name "unconnected-(J700-HSOp(5)-PadB37)") (class "Default")
      (node (ref "J700") (pin "B37") (pinfunction "HSOp(5)_B37") (pintype "input+no_connect"))
    )
    (net (code "85") (name "unconnected-(J700-HSOp(6)-PadB41)") (class "Default")
      (node (ref "J700") (pin "B41") (pinfunction "HSOp(6)_B41") (pintype "input+no_connect"))
    )
    (net (code "86") (name "unconnected-(J700-HSOp(7)-PadB45)") (class "Default")
      (node (ref "J700") (pin "B45") (pinfunction "HSOp(7)_B45") (pintype "input+no_connect"))
    )
    (net (code "87") (name "unconnected-(J700-HSOp(8)-PadB50)") (class "Default")
      (node (ref "J700") (pin "B50") (pinfunction "HSOp(8)_B50") (pintype "input+no_connect"))
    )
    (net (code "88") (name "unconnected-(J700-HSOp(9)-PadB54)") (class "Default")
      (node (ref "J700") (pin "B54") (pinfunction "HSOp(9)_B54") (pintype "input+no_connect"))
    )
    (net (code "89") (name "unconnected-(J700-HSOp(10)-PadB58)") (class "Default")
      (node (ref "J700") (pin "B58") (pinfunction "HSOp(10)_B58") (pintype "input+no_connect"))
    )
    (net (code "90") (name "unconnected-(J700-HSOp(11)-PadB62)") (class "Default")
      (node (ref "J700") (pin "B62") (pinfunction "HSOp(11)_B62") (pintype "input+no_connect"))
    )
    (net (code "91") (name "unconnected-(J700-HSOp(12)-PadB66)") (class "Default")
      (node (ref "J700") (pin "B66") (pinfunction "HSOp(12)_B66") (pintype "input+no_connect"))
    )
    (net (code "92") (name "unconnected-(J700-HSOp(13)-PadB70)") (class "Default")
      (node (ref "J700") (pin "B70") (pinfunction "HSOp(13)_B70") (pintype "input+no_connect"))
    )
    (net (code "93") (name "unconnected-(J700-HSOp(14)-PadB74)") (class "Default")
      (node (ref "J700") (pin "B74") (pinfunction "HSOp(14)_B74") (pintype "input+no_connect"))
    )
    (net (code "94") (name "unconnected-(J700-HSOp(15)-PadB78)") (class "Default")
      (node (ref "J700") (pin "B78") (pinfunction "HSOp(15)_B78") (pintype "input+no_connect"))
    )
    (net (code "95") (name "unconnected-(J700-RSVD#2-PadB82)") (class "Default")
      (node (ref "J700") (pin "B82") (pinfunction "RSVD#2_B82") (pintype "passive+no_connect"))
    )
    (net (code "96") (name "unconnected-(J700-RSVD-PadA19)") (class "Default")
      (node (ref "J700") (pin "A19") (pinfunction "RSVD_A19") (pintype "passive+no_connect"))
    )
    (net (code "97") (name "unconnected-(J700-RSVD-PadA32)") (class "Default")
      (node (ref "J700") (pin "A32") (pinfunction "RSVD_A32") (pintype "input+no_connect"))
    )
    (net (code "98") (name "unconnected-(J700-RSVD-PadA33)") (class "Default")
      (node (ref "J700") (pin "A33") (pinfunction "RSVD_A33") (pintype "output+no_connect"))
    )
    (net (code "99") (name "unconnected-(J700-RSVD-PadA50)") (class "Default")
      (node (ref "J700") (pin "A50") (pinfunction "RSVD_A50") (pintype "passive"))
    )
    (net (code "100") (name "unconnected-(J700-RSVD-PadB12)") (class "Default")
      (node (ref "J700") (pin "B12") (pinfunction "RSVD_B12") (pintype "passive+no_connect"))
    )
    (net (code "101") (name "unconnected-(J700-RSVD-PadB30)") (class "Default")
      (node (ref "J700") (pin "B30") (pinfunction "RSVD_B30") (pintype "passive+no_connect"))
    )
    (net (code "102") (name "unconnected-(J700-SMCLK-PadB5)") (class "Default")
      (node (ref "J700") (pin "B5") (pinfunction "SMCLK_B5") (pintype "input+no_connect"))
    )
    (net (code "103") (name "unconnected-(J700-SMDAT-PadB6)") (class "Default")
      (node (ref "J700") (pin "B6") (pinfunction "SMDAT_B6") (pintype "bidirectional+no_connect"))
    )
  )
)
